# PiZeroHub.net
KiCad netlist of a schematic drawn in EAGLE
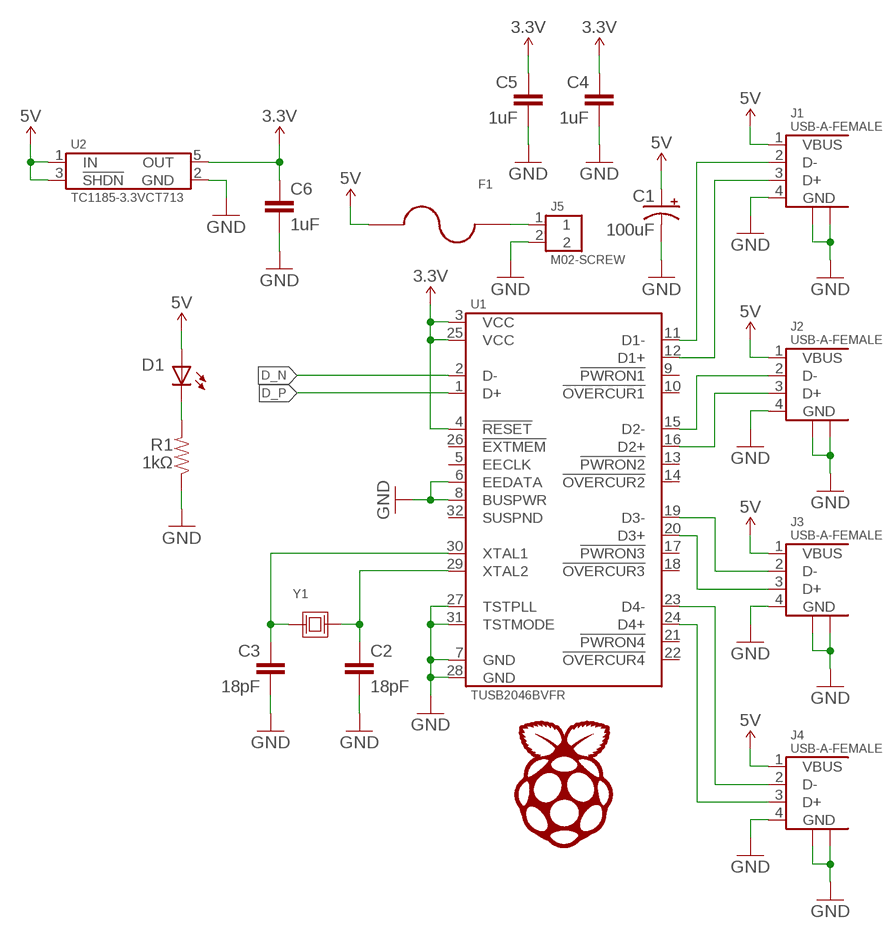
[diagram p0: schematic, sheet 1]

(export (version "E")
  (design (tool "Eeschema 10.0.6"))
  (components
    (comp (ref "C1")
      (value "100uF")
      (footprint "eagle-import:CAP_POL-6.6X6.6")
      (libsource (lib "eagle-import") (part "CAP_POL-6.6X6.6"))
    )
    (comp (ref "C2")
      (value "18pF")
      (footprint "eagle-import:0805-CAP")
      (libsource (lib "eagle-import") (part "CAP-0805"))
    )
    (comp (ref "C3")
      (value "18pF")
      (footprint "eagle-import:0805-CAP")
      (libsource (lib "eagle-import") (part "CAP-0805"))
    )
    (comp (ref "C4")
      (value "1uF")
      (footprint "eagle-import:0805-CAP")
      (libsource (lib "eagle-import") (part "CAP-0805"))
    )
    (comp (ref "C5")
      (value "1uF")
      (footprint "eagle-import:0805-CAP")
      (libsource (lib "eagle-import") (part "CAP-0805"))
    )
    (comp (ref "C6")
      (value "1uF")
      (footprint "eagle-import:0805-CAP")
      (libsource (lib "eagle-import") (part "CAP-0805"))
    )
    (comp (ref "D1")
      (value "LED-0805")
      (footprint "eagle-import:0805-LED")
      (libsource (lib "eagle-import") (part "LED-0805"))
    )
    (comp (ref "F1")
      (value "PTC-1812")
      (footprint "eagle-import:1812-PTC")
      (libsource (lib "eagle-import") (part "PTC-1812"))
    )
    (comp (ref "J1")
      (value "USB-A-FEMALE")
      (footprint "eagle-import:USB-A-FEMALE")
      (libsource (lib "eagle-import") (part "USB-A-FEMALE"))
    )
    (comp (ref "J2")
      (value "USB-A-FEMALE")
      (footprint "eagle-import:USB-A-FEMALE")
      (libsource (lib "eagle-import") (part "USB-A-FEMALE"))
    )
    (comp (ref "J3")
      (value "USB-A-FEMALE")
      (footprint "eagle-import:USB-A-FEMALE")
      (libsource (lib "eagle-import") (part "USB-A-FEMALE"))
    )
    (comp (ref "J4")
      (value "USB-A-FEMALE")
      (footprint "eagle-import:USB-A-FEMALE")
      (libsource (lib "eagle-import") (part "USB-A-FEMALE"))
    )
    (comp (ref "J5")
      (value "M02-SCREW")
      (footprint "eagle-import:M02-SCREW")
      (libsource (lib "eagle-import") (part "M02-SCREW"))
    )
    (comp (ref "R1")
      (value "1kΩ")
      (footprint "eagle-import:0805-RES")
      (libsource (lib "eagle-import") (part "RESISTOR-0805"))
    )
    (comp (ref "U$1")
      (value "RPI-ZERO_NOPAD")
      (footprint "eagle-import:RPI_ZERO-NOPADS")
      (libsource (lib "eagle-import") (part "RPI-ZERO_NOPAD"))
    )
    (comp (ref "U1")
      (value "TUSB2046BVFR")
      (footprint "eagle-import:LQFP-32")
      (libsource (lib "eagle-import") (part "TUSB2046BVFR"))
    )
    (comp (ref "U2")
      (value "TC1185-3.3VCT713")
      (footprint "eagle-import:SOT23-5")
      (libsource (lib "eagle-import") (part "TC1185-3.3VCT713"))
    )
    (comp (ref "Y1")
      (value "CRYSTAL2-HC49")
      (footprint "eagle-import:HC49_US")
      (libsource (lib "eagle-import") (part "CRYSTAL2-HC49"))
    )
  )
  (nets
    (net (code "1") (name "3.3V") (class "Default")
      (node (ref "C4") (pin "1") (pinfunction "1_1") (pintype "passive"))
      (node (ref "C5") (pin "1") (pinfunction "1_1") (pintype "passive"))
      (node (ref "C6") (pin "1") (pinfunction "1_1") (pintype "passive"))
      (node (ref "U1") (pin "25") (pinfunction "VCC_25") (pintype "bidirectional"))
      (node (ref "U1") (pin "3") (pinfunction "VCC_3") (pintype "bidirectional"))
      (node (ref "U1") (pin "4") (pinfunction "~{RESET}_4") (pintype "bidirectional"))
      (node (ref "U2") (pin "5") (pinfunction "OUT_5") (pintype "bidirectional"))
    )
    (net (code "2") (name "5V") (class "Default")
      (node (ref "C1") (pin "+") (pinfunction "+_+") (pintype "passive"))
      (node (ref "D1") (pin "A") (pinfunction "A_A") (pintype "passive"))
      (node (ref "F1") (pin "2") (pinfunction "2_2") (pintype "bidirectional"))
      (node (ref "J1") (pin "1") (pinfunction "VBUS_1") (pintype "bidirectional"))
      (node (ref "J2") (pin "1") (pinfunction "VBUS_1") (pintype "bidirectional"))
      (node (ref "J3") (pin "1") (pinfunction "VBUS_1") (pintype "bidirectional"))
      (node (ref "J4") (pin "1") (pinfunction "VBUS_1") (pintype "bidirectional"))
      (node (ref "U2") (pin "1") (pinfunction "IN_1") (pintype "bidirectional"))
      (node (ref "U2") (pin "3") (pinfunction "~{SHDN}_3") (pintype "bidirectional"))
    )
    (net (code "3") (name "D_N") (class "Default")
      (node (ref "U1") (pin "2") (pinfunction "D-_2") (pintype "bidirectional"))
    )
    (net (code "4") (name "D_P") (class "Default")
      (node (ref "U1") (pin "1") (pinfunction "D+_1") (pintype "bidirectional"))
    )
    (net (code "5") (name "GND") (class "Default")
      (node (ref "C1") (pin "-") (pinfunction "-_-") (pintype "passive"))
      (node (ref "C2") (pin "2") (pinfunction "2_2") (pintype "passive"))
      (node (ref "C3") (pin "2") (pinfunction "2_2") (pintype "passive"))
      (node (ref "C4") (pin "2") (pinfunction "2_2") (pintype "passive"))
      (node (ref "C5") (pin "2") (pinfunction "2_2") (pintype "passive"))
      (node (ref "C6") (pin "2") (pinfunction "2_2") (pintype "passive"))
      (node (ref "J1") (pin "4") (pinfunction "GND_4") (pintype "bidirectional"))
      (node (ref "J1") (pin "P$1") (pinfunction "P$1_P$1") (pintype "bidirectional"))
      (node (ref "J1") (pin "P$2") (pinfunction "P$2_P$2") (pintype "bidirectional"))
      (node (ref "J2") (pin "4") (pinfunction "GND_4") (pintype "bidirectional"))
      (node (ref "J2") (pin "P$1") (pinfunction "P$1_P$1") (pintype "bidirectional"))
      (node (ref "J2") (pin "P$2") (pinfunction "P$2_P$2") (pintype "bidirectional"))
      (node (ref "J3") (pin "4") (pinfunction "GND_4") (pintype "bidirectional"))
      (node (ref "J3") (pin "P$1") (pinfunction "P$1_P$1") (pintype "bidirectional"))
      (node (ref "J3") (pin "P$2") (pinfunction "P$2_P$2") (pintype "bidirectional"))
      (node (ref "J4") (pin "4") (pinfunction "GND_4") (pintype "bidirectional"))
      (node (ref "J4") (pin "P$1") (pinfunction "P$1_P$1") (pintype "bidirectional"))
      (node (ref "J4") (pin "P$2") (pinfunction "P$2_P$2") (pintype "bidirectional"))
      (node (ref "J5") (pin "2") (pinfunction "2_2") (pintype "bidirectional"))
      (node (ref "R1") (pin "1") (pinfunction "1_1") (pintype "passive"))
      (node (ref "U1") (pin "27") (pinfunction "TSTPLL_27") (pintype "bidirectional"))
      (node (ref "U1") (pin "28") (pinfunction "GND_28") (pintype "bidirectional"))
      (node (ref "U1") (pin "31") (pinfunction "TSTMODE_31") (pintype "bidirectional"))
      (node (ref "U1") (pin "6") (pinfunction "EEDATA_6") (pintype "bidirectional"))
      (node (ref "U1") (pin "7") (pinfunction "GND_7") (pintype "bidirectional"))
      (node (ref "U1") (pin "8") (pinfunction "BUSPWR_8") (pintype "bidirectional"))
      (node (ref "U2") (pin "2") (pinfunction "GND_2") (pintype "bidirectional"))
    )
    (net (code "6") (name "Net-(D1-PadC)") (class "Default")
      (node (ref "D1") (pin "C") (pinfunction "C_C") (pintype "passive"))
      (node (ref "R1") (pin "2") (pinfunction "2_2") (pintype "passive"))
    )
    (net (code "7") (name "Net-(F1-Pad1)") (class "Default")
      (node (ref "F1") (pin "1") (pinfunction "1_1") (pintype "bidirectional"))
      (node (ref "J5") (pin "1") (pinfunction "1_1") (pintype "bidirectional"))
    )
    (net (code "8") (name "Net-(J1-D+)") (class "Default")
      (node (ref "J1") (pin "3") (pinfunction "D+_3") (pintype "bidirectional"))
      (node (ref "U1") (pin "12") (pinfunction "D1+_12") (pintype "bidirectional"))
    )
    (net (code "9") (name "Net-(J1-D-)") (class "Default")
      (node (ref "J1") (pin "2") (pinfunction "D-_2") (pintype "bidirectional"))
      (node (ref "U1") (pin "11") (pinfunction "D1-_11") (pintype "bidirectional"))
    )
    (net (code "10") (name "Net-(J2-D+)") (class "Default")
      (node (ref "J2") (pin "3") (pinfunction "D+_3") (pintype "bidirectional"))
      (node (ref "U1") (pin "16") (pinfunction "D2+_16") (pintype "bidirectional"))
    )
    (net (code "11") (name "Net-(J2-D-)") (class "Default")
      (node (ref "J2") (pin "2") (pinfunction "D-_2") (pintype "bidirectional"))
      (node (ref "U1") (pin "15") (pinfunction "D2-_15") (pintype "bidirectional"))
    )
    (net (code "12") (name "Net-(J3-D+)") (class "Default")
      (node (ref "J3") (pin "3") (pinfunction "D+_3") (pintype "bidirectional"))
      (node (ref "U1") (pin "20") (pinfunction "D3+_20") (pintype "bidirectional"))
    )
    (net (code "13") (name "Net-(J3-D-)") (class "Default")
      (node (ref "J3") (pin "2") (pinfunction "D-_2") (pintype "bidirectional"))
      (node (ref "U1") (pin "19") (pinfunction "D3-_19") (pintype "bidirectional"))
    )
    (net (code "14") (name "Net-(J4-D+)") (class "Default")
      (node (ref "J4") (pin "3") (pinfunction "D+_3") (pintype "bidirectional"))
      (node (ref "U1") (pin "24") (pinfunction "D4+_24") (pintype "bidirectional"))
    )
    (net (code "15") (name "Net-(J4-D-)") (class "Default")
      (node (ref "J4") (pin "2") (pinfunction "D-_2") (pintype "bidirectional"))
      (node (ref "U1") (pin "23") (pinfunction "D4-_23") (pintype "bidirectional"))
    )
    (net (code "16") (name "Net-(U1-XTAL1)") (class "Default")
      (node (ref "C3") (pin "1") (pinfunction "1_1") (pintype "passive"))
      (node (ref "U1") (pin "30") (pinfunction "XTAL1_30") (pintype "bidirectional"))
      (node (ref "Y1") (pin "1") (pinfunction "1_1") (pintype "bidirectional"))
    )
    (net (code "17") (name "Net-(U1-XTAL2)") (class "Default")
      (node (ref "C2") (pin "1") (pinfunction "1_1") (pintype "passive"))
      (node (ref "U1") (pin "29") (pinfunction "XTAL2_29") (pintype "bidirectional"))
      (node (ref "Y1") (pin "2") (pinfunction "2_2") (pintype "bidirectional"))
    )
    (net (code "18") (name "unconnected-(U1-EECLK-Pad5)") (class "Default")
      (node (ref "U1") (pin "5") (pinfunction "EECLK_5") (pintype "bidirectional"))
    )
    (net (code "19") (name "unconnected-(U1-SUSPND-Pad32)") (class "Default")
      (node (ref "U1") (pin "32") (pinfunction "SUSPND_32") (pintype "bidirectional"))
    )
    (net (code "20") (name "unconnected-(U1-~{EXTMEM}-Pad26)") (class "Default")
      (node (ref "U1") (pin "26") (pinfunction "~{EXTMEM}_26") (pintype "bidirectional"))
    )
    (net (code "21") (name "unconnected-(U1-~{OVERCUR1}-Pad10)") (class "Default")
      (node (ref "U1") (pin "10") (pinfunction "~{OVERCUR1}_10") (pintype "bidirectional"))
    )
    (net (code "22") (name "unconnected-(U1-~{OVERCUR2}-Pad14)") (class "Default")
      (node (ref "U1") (pin "14") (pinfunction "~{OVERCUR2}_14") (pintype "bidirectional"))
    )
    (net (code "23") (name "unconnected-(U1-~{OVERCUR3}-Pad18)") (class "Default")
      (node (ref "U1") (pin "18") (pinfunction "~{OVERCUR3}_18") (pintype "bidirectional"))
    )
    (net (code "24") (name "unconnected-(U1-~{OVERCUR4}-Pad22)") (class "Default")
      (node (ref "U1") (pin "22") (pinfunction "~{OVERCUR4}_22") (pintype "bidirectional"))
    )
    (net (code "25") (name "unconnected-(U1-~{PWRON1}-Pad9)") (class "Default")
      (node (ref "U1") (pin "9") (pinfunction "~{PWRON1}_9") (pintype "bidirectional"))
    )
    (net (code "26") (name "unconnected-(U1-~{PWRON2}-Pad13)") (class "Default")
      (node (ref "U1") (pin "13") (pinfunction "~{PWRON2}_13") (pintype "bidirectional"))
    )
    (net (code "27") (name "unconnected-(U1-~{PWRON3}-Pad17)") (class "Default")
      (node (ref "U1") (pin "17") (pinfunction "~{PWRON3}_17") (pintype "bidirectional"))
    )
    (net (code "28") (name "unconnected-(U1-~{PWRON4}-Pad21)") (class "Default")
      (node (ref "U1") (pin "21") (pinfunction "~{PWRON4}_21") (pintype "bidirectional"))
    )
  )
)
